# 8_led_51.net
KiCad netlist of a schematic drawn in EasyEDA Pro
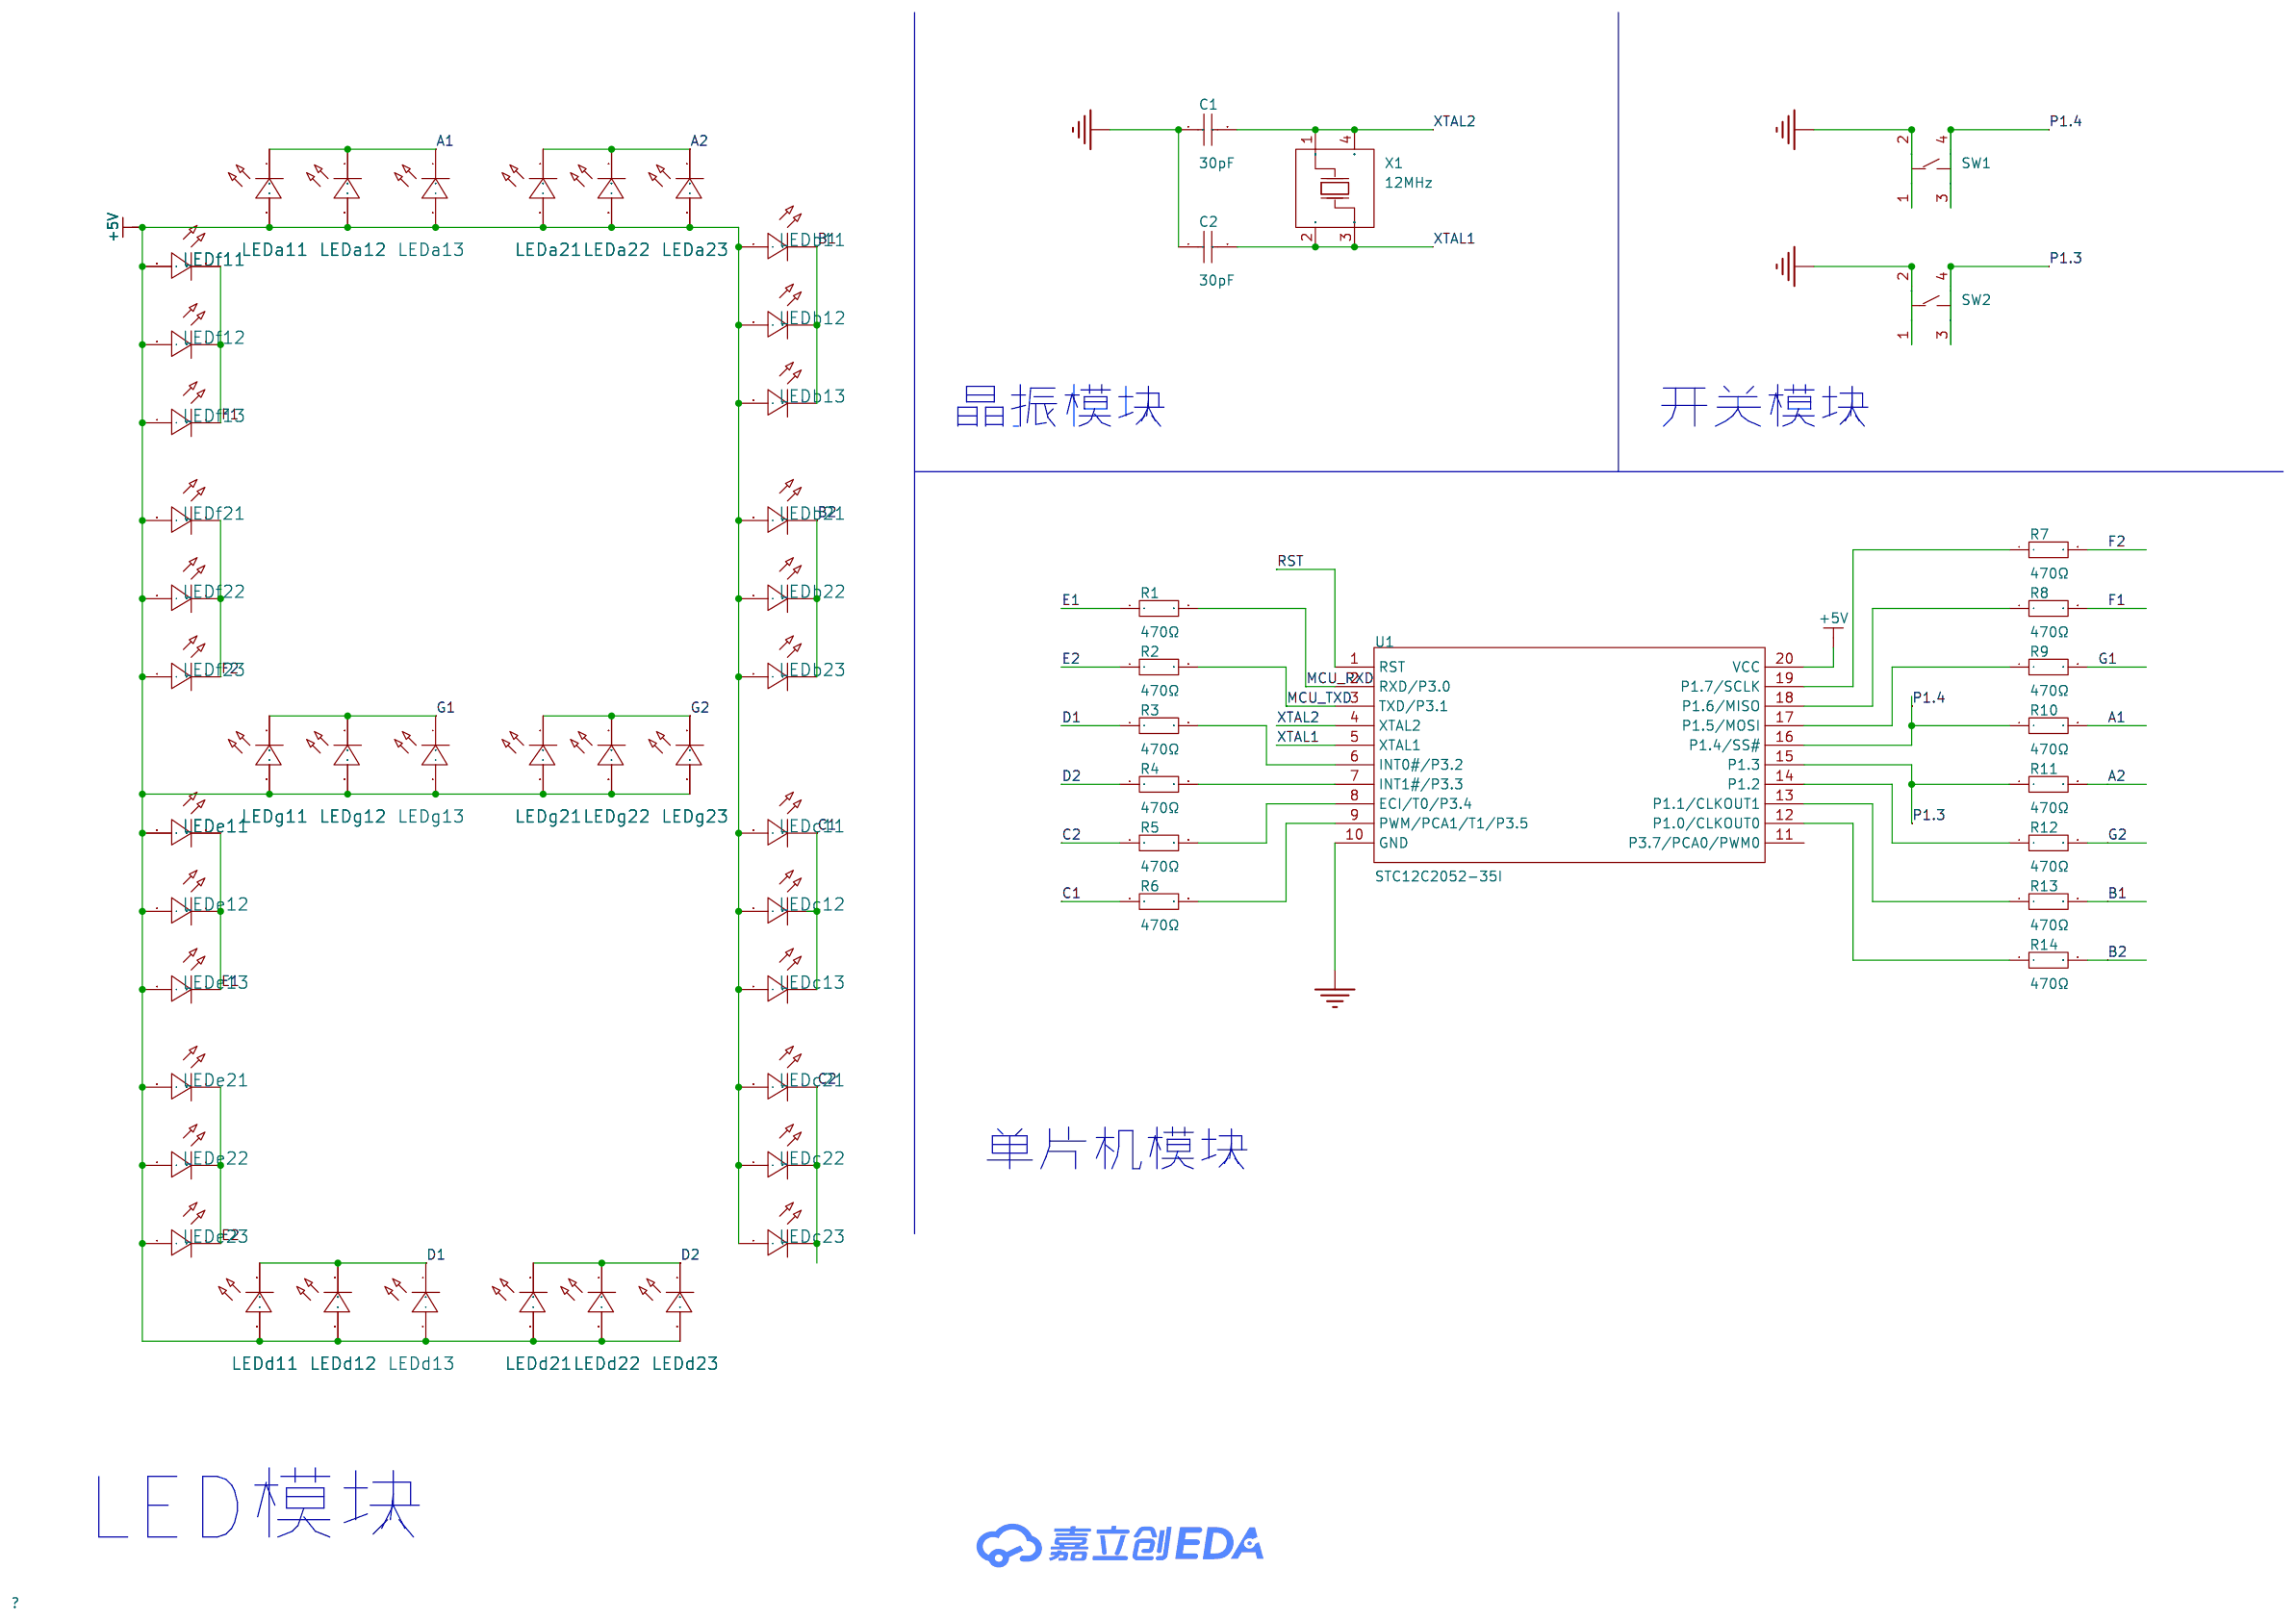
[diagram p0: 主体]
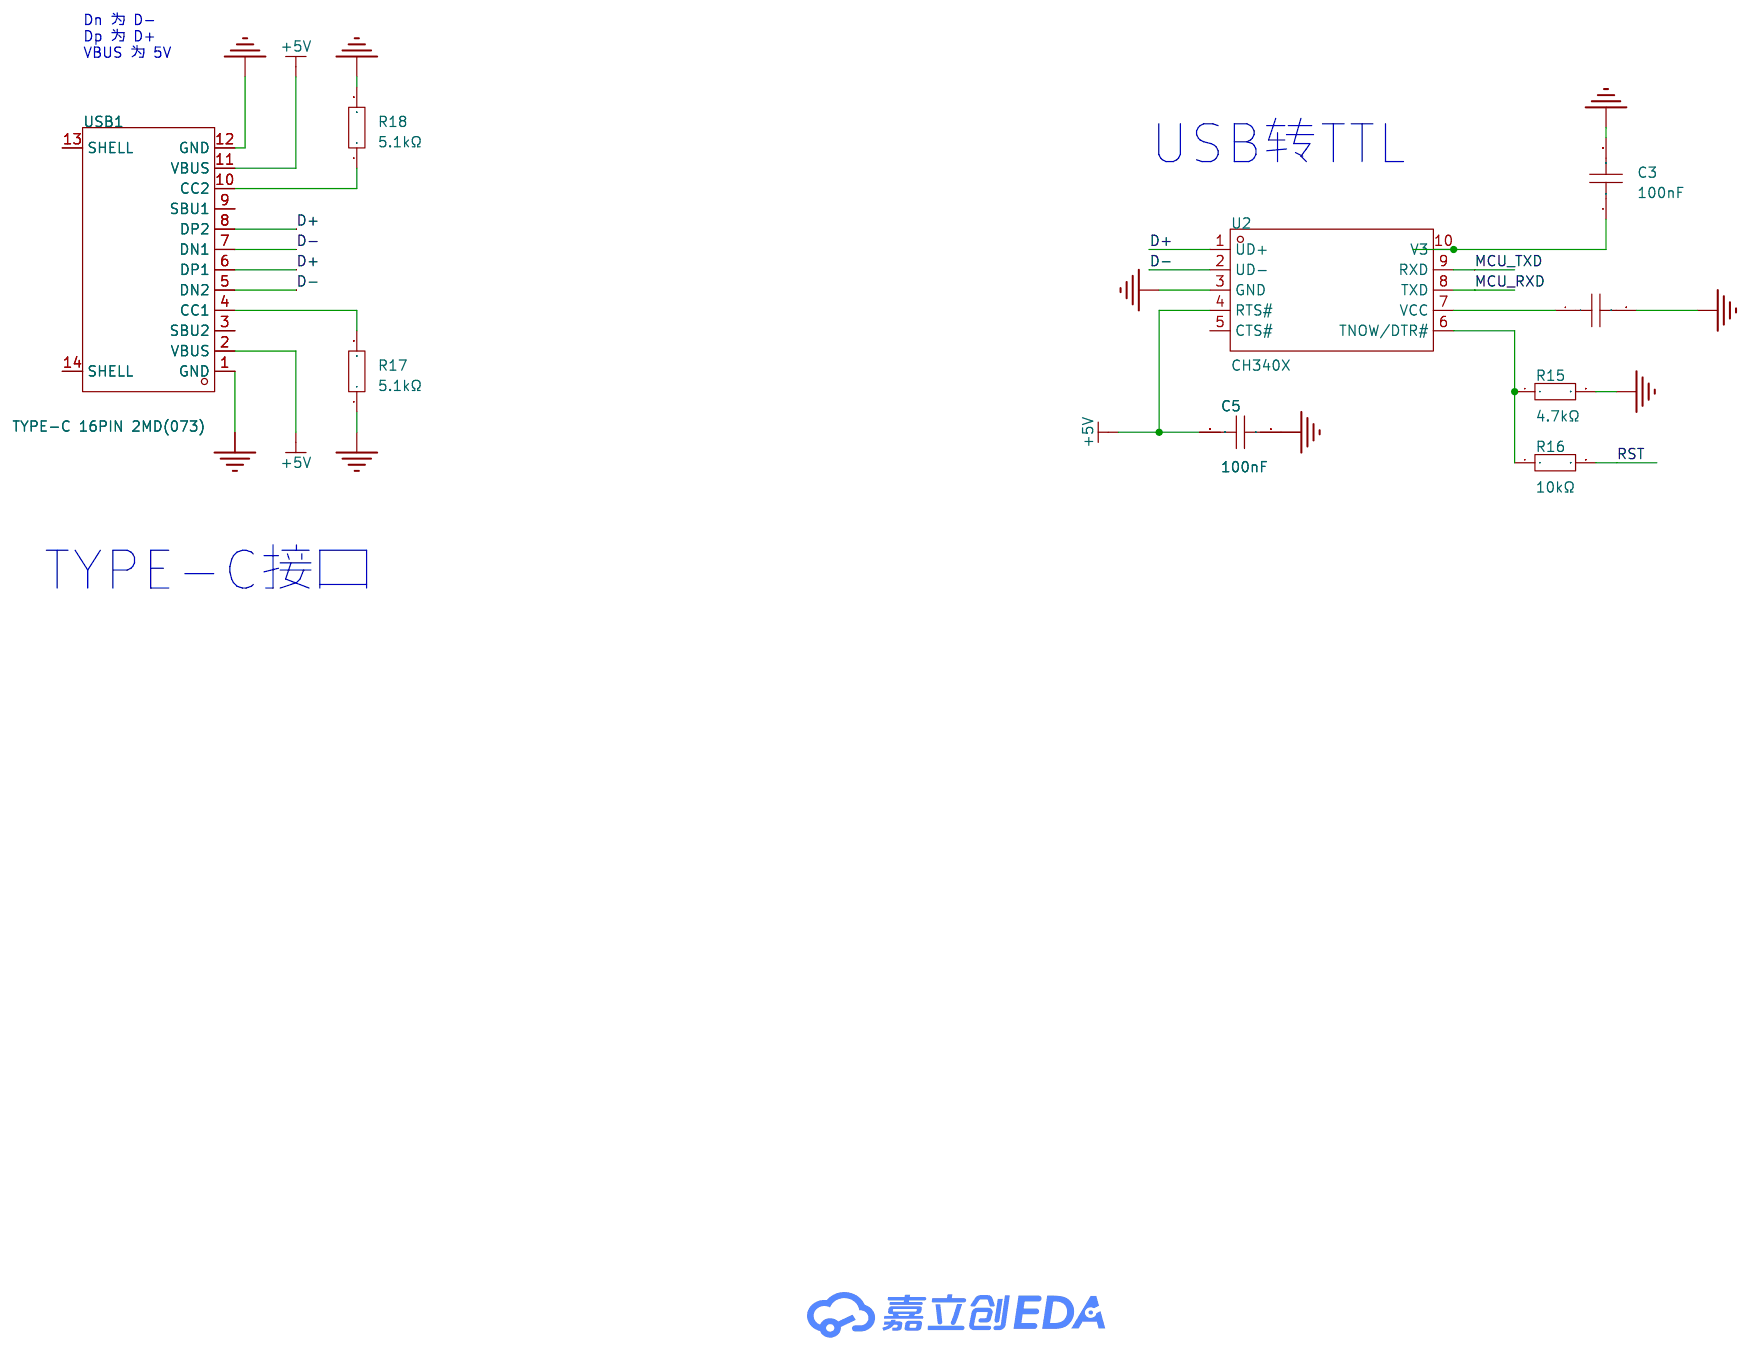
[diagram p1: P2]

(export (version "E")
  (design (tool "Eeschema 10.0.6"))
  (components
    (comp (ref "C1")
      (value "30pF")
      (footprint "easyedapro:C0805")
      (description "容值:30pF;精度:±5%;额定电压:50V;温度系数:C0G;")
      (fields (field (name "Manufacturer Part") "0805CG300J500NT") (field (name "Manufacturer") "FH(风华)"))
      (libsource (lib "easyedapro") (part "0805CG300J500NT"))
    )
    (comp (ref "C2")
      (value "30pF")
      (footprint "easyedapro:C0805")
      (description "容值:30pF;精度:±5%;额定电压:50V;温度系数:C0G;")
      (fields (field (name "Manufacturer Part") "0805CG300J500NT") (field (name "Manufacturer") "FH(风华)"))
      (libsource (lib "easyedapro") (part "0805CG300J500NT"))
    )
    (comp (ref "LEDa11")
      (value "~")
      (footprint "easyedapro:LED_0603")
      (libsource (lib "easyedapro") (part "LED_R"))
    )
    (comp (ref "LEDa12")
      (value "~")
      (footprint "easyedapro:LED_0603")
      (libsource (lib "easyedapro") (part "LED_R"))
    )
    (comp (ref "LEDa13")
      (value "~")
      (footprint "easyedapro:LED_0603")
      (libsource (lib "easyedapro") (part "LED_R"))
    )
    (comp (ref "LEDa21")
      (value "~")
      (footprint "easyedapro:LED_0603")
      (libsource (lib "easyedapro") (part "LED_R"))
    )
    (comp (ref "LEDa22")
      (value "~")
      (footprint "easyedapro:LED_0603")
      (libsource (lib "easyedapro") (part "LED_R"))
    )
    (comp (ref "LEDa23")
      (value "~")
      (footprint "easyedapro:LED_0603")
      (libsource (lib "easyedapro") (part "LED_R"))
    )
    (comp (ref "LEDb11")
      (value "~")
      (footprint "easyedapro:LED_0603")
      (libsource (lib "easyedapro") (part "LED_R"))
    )
    (comp (ref "LEDb12")
      (value "~")
      (footprint "easyedapro:LED_0603")
      (libsource (lib "easyedapro") (part "LED_R"))
    )
    (comp (ref "LEDb13")
      (value "~")
      (footprint "easyedapro:LED_0603")
      (libsource (lib "easyedapro") (part "LED_R"))
    )
    (comp (ref "LEDb21")
      (value "~")
      (footprint "easyedapro:LED_0603")
      (libsource (lib "easyedapro") (part "LED_R"))
    )
    (comp (ref "LEDb22")
      (value "~")
      (footprint "easyedapro:LED_0603")
      (libsource (lib "easyedapro") (part "LED_R"))
    )
    (comp (ref "LEDb23")
      (value "~")
      (footprint "easyedapro:LED_0603")
      (libsource (lib "easyedapro") (part "LED_R"))
    )
    (comp (ref "LEDc11")
      (value "~")
      (footprint "easyedapro:LED_0603")
      (libsource (lib "easyedapro") (part "LED_R"))
    )
    (comp (ref "LEDc12")
      (value "~")
      (footprint "easyedapro:LED_0603")
      (libsource (lib "easyedapro") (part "LED_R"))
    )
    (comp (ref "LEDc13")
      (value "~")
      (footprint "easyedapro:LED_0603")
      (libsource (lib "easyedapro") (part "LED_R"))
    )
    (comp (ref "LEDc21")
      (value "~")
      (footprint "easyedapro:LED_0603")
      (libsource (lib "easyedapro") (part "LED_R"))
    )
    (comp (ref "LEDc22")
      (value "~")
      (footprint "easyedapro:LED_0603")
      (libsource (lib "easyedapro") (part "LED_R"))
    )
    (comp (ref "LEDc23")
      (value "~")
      (footprint "easyedapro:LED_0603")
      (libsource (lib "easyedapro") (part "LED_R"))
    )
    (comp (ref "LEDd11")
      (value "~")
      (footprint "easyedapro:LED_0603")
      (libsource (lib "easyedapro") (part "LED_R"))
    )
    (comp (ref "LEDd12")
      (value "~")
      (footprint "easyedapro:LED_0603")
      (libsource (lib "easyedapro") (part "LED_R"))
    )
    (comp (ref "LEDd13")
      (value "~")
      (footprint "easyedapro:LED_0603")
      (libsource (lib "easyedapro") (part "LED_R"))
    )
    (comp (ref "LEDd21")
      (value "~")
      (footprint "easyedapro:LED_0603")
      (libsource (lib "easyedapro") (part "LED_R"))
    )
    (comp (ref "LEDd22")
      (value "~")
      (footprint "easyedapro:LED_0603")
      (libsource (lib "easyedapro") (part "LED_R"))
    )
    (comp (ref "LEDd23")
      (value "~")
      (footprint "easyedapro:LED_0603")
      (libsource (lib "easyedapro") (part "LED_R"))
    )
    (comp (ref "LEDe11")
      (value "~")
      (footprint "easyedapro:LED_0603")
      (libsource (lib "easyedapro") (part "LED_R"))
    )
    (comp (ref "LEDe12")
      (value "~")
      (footprint "easyedapro:LED_0603")
      (libsource (lib "easyedapro") (part "LED_R"))
    )
    (comp (ref "LEDe13")
      (value "~")
      (footprint "easyedapro:LED_0603")
      (libsource (lib "easyedapro") (part "LED_R"))
    )
    (comp (ref "LEDe21")
      (value "~")
      (footprint "easyedapro:LED_0603")
      (libsource (lib "easyedapro") (part "LED_R"))
    )
    (comp (ref "LEDe22")
      (value "~")
      (footprint "easyedapro:LED_0603")
      (libsource (lib "easyedapro") (part "LED_R"))
    )
    (comp (ref "LEDe23")
      (value "~")
      (footprint "easyedapro:LED_0603")
      (libsource (lib "easyedapro") (part "LED_R"))
    )
    (comp (ref "LEDf11")
      (value "~")
      (footprint "easyedapro:LED_0603")
      (libsource (lib "easyedapro") (part "LED_R"))
    )
    (comp (ref "LEDf12")
      (value "~")
      (footprint "easyedapro:LED_0603")
      (libsource (lib "easyedapro") (part "LED_R"))
    )
    (comp (ref "LEDf13")
      (value "~")
      (footprint "easyedapro:LED_0603")
      (libsource (lib "easyedapro") (part "LED_R"))
    )
    (comp (ref "LEDf21")
      (value "~")
      (footprint "easyedapro:LED_0603")
      (libsource (lib "easyedapro") (part "LED_R"))
    )
    (comp (ref "LEDf22")
      (value "~")
      (footprint "easyedapro:LED_0603")
      (libsource (lib "easyedapro") (part "LED_R"))
    )
    (comp (ref "LEDf23")
      (value "~")
      (footprint "easyedapro:LED_0603")
      (libsource (lib "easyedapro") (part "LED_R"))
    )
    (comp (ref "LEDg11")
      (value "~")
      (footprint "easyedapro:LED_0603")
      (libsource (lib "easyedapro") (part "LED_R"))
    )
    (comp (ref "LEDg12")
      (value "~")
      (footprint "easyedapro:LED_0603")
      (libsource (lib "easyedapro") (part "LED_R"))
    )
    (comp (ref "LEDg13")
      (value "~")
      (footprint "easyedapro:LED_0603")
      (libsource (lib "easyedapro") (part "LED_R"))
    )
    (comp (ref "LEDg21")
      (value "~")
      (footprint "easyedapro:LED_0603")
      (libsource (lib "easyedapro") (part "LED_R"))
    )
    (comp (ref "LEDg22")
      (value "~")
      (footprint "easyedapro:LED_0603")
      (libsource (lib "easyedapro") (part "LED_R"))
    )
    (comp (ref "LEDg23")
      (value "~")
      (footprint "easyedapro:LED_0603")
      (libsource (lib "easyedapro") (part "LED_R"))
    )
    (comp (ref "R1")
      (value "470Ω")
      (footprint "easyedapro:R0805")
      (description "电阻类型:厚膜电阻;阻值:470Ω;精度:±1%;功率:125mW;工作电压:150V;温度系数:±100ppm/°C;")
      (fields
        (field (name "Manufacturer Part") "0805W8F4700T5E")
        (field (name "Manufacturer") "UNI-ROYAL(厚声)")
      )
      (libsource (lib "easyedapro") (part "0805W8F4700T5E"))
    )
    (comp (ref "R2")
      (value "470Ω")
      (footprint "easyedapro:R0805")
      (description "电阻类型:厚膜电阻;阻值:470Ω;精度:±1%;功率:125mW;工作电压:150V;温度系数:±100ppm/°C;")
      (fields
        (field (name "Manufacturer Part") "0805W8F4700T5E")
        (field (name "Manufacturer") "UNI-ROYAL(厚声)")
      )
      (libsource (lib "easyedapro") (part "0805W8F4700T5E"))
    )
    (comp (ref "R3")
      (value "470Ω")
      (footprint "easyedapro:R0805")
      (description "电阻类型:厚膜电阻;阻值:470Ω;精度:±1%;功率:125mW;工作电压:150V;温度系数:±100ppm/°C;")
      (fields
        (field (name "Manufacturer Part") "0805W8F4700T5E")
        (field (name "Manufacturer") "UNI-ROYAL(厚声)")
      )
      (libsource (lib "easyedapro") (part "0805W8F4700T5E"))
    )
    (comp (ref "R4")
      (value "470Ω")
      (footprint "easyedapro:R0805")
      (description "电阻类型:厚膜电阻;阻值:470Ω;精度:±1%;功率:125mW;工作电压:150V;温度系数:±100ppm/°C;")
      (fields
        (field (name "Manufacturer Part") "0805W8F4700T5E")
        (field (name "Manufacturer") "UNI-ROYAL(厚声)")
      )
      (libsource (lib "easyedapro") (part "0805W8F4700T5E"))
    )
    (comp (ref "R5")
      (value "470Ω")
      (footprint "easyedapro:R0805")
      (description "电阻类型:厚膜电阻;阻值:470Ω;精度:±1%;功率:125mW;工作电压:150V;温度系数:±100ppm/°C;")
      (fields
        (field (name "Manufacturer Part") "0805W8F4700T5E")
        (field (name "Manufacturer") "UNI-ROYAL(厚声)")
      )
      (libsource (lib "easyedapro") (part "0805W8F4700T5E"))
    )
    (comp (ref "R6")
      (value "470Ω")
      (footprint "easyedapro:R0805")
      (description "电阻类型:厚膜电阻;阻值:470Ω;精度:±1%;功率:125mW;工作电压:150V;温度系数:±100ppm/°C;")
      (fields
        (field (name "Manufacturer Part") "0805W8F4700T5E")
        (field (name "Manufacturer") "UNI-ROYAL(厚声)")
      )
      (libsource (lib "easyedapro") (part "0805W8F4700T5E"))
    )
    (comp (ref "R7")
      (value "470Ω")
      (footprint "easyedapro:R0805")
      (description "电阻类型:厚膜电阻;阻值:470Ω;精度:±1%;功率:125mW;工作电压:150V;温度系数:±100ppm/°C;")
      (fields
        (field (name "Manufacturer Part") "0805W8F4700T5E")
        (field (name "Manufacturer") "UNI-ROYAL(厚声)")
      )
      (libsource (lib "easyedapro") (part "0805W8F4700T5E"))
    )
    (comp (ref "R8")
      (value "470Ω")
      (footprint "easyedapro:R0805")
      (description "电阻类型:厚膜电阻;阻值:470Ω;精度:±1%;功率:125mW;工作电压:150V;温度系数:±100ppm/°C;")
      (fields
        (field (name "Manufacturer Part") "0805W8F4700T5E")
        (field (name "Manufacturer") "UNI-ROYAL(厚声)")
      )
      (libsource (lib "easyedapro") (part "0805W8F4700T5E"))
    )
    (comp (ref "R9")
      (value "470Ω")
      (footprint "easyedapro:R0805")
      (description "电阻类型:厚膜电阻;阻值:470Ω;精度:±1%;功率:125mW;工作电压:150V;温度系数:±100ppm/°C;")
      (fields
        (field (name "Manufacturer Part") "0805W8F4700T5E")
        (field (name "Manufacturer") "UNI-ROYAL(厚声)")
      )
      (libsource (lib "easyedapro") (part "0805W8F4700T5E"))
    )
    (comp (ref "R10")
      (value "470Ω")
      (footprint "easyedapro:R0805")
      (description "电阻类型:厚膜电阻;阻值:470Ω;精度:±1%;功率:125mW;工作电压:150V;温度系数:±100ppm/°C;")
      (fields
        (field (name "Manufacturer Part") "0805W8F4700T5E")
        (field (name "Manufacturer") "UNI-ROYAL(厚声)")
      )
      (libsource (lib "easyedapro") (part "0805W8F4700T5E"))
    )
    (comp (ref "R11")
      (value "470Ω")
      (footprint "easyedapro:R0805")
      (description "电阻类型:厚膜电阻;阻值:470Ω;精度:±1%;功率:125mW;工作电压:150V;温度系数:±100ppm/°C;")
      (fields
        (field (name "Manufacturer Part") "0805W8F4700T5E")
        (field (name "Manufacturer") "UNI-ROYAL(厚声)")
      )
      (libsource (lib "easyedapro") (part "0805W8F4700T5E"))
    )
    (comp (ref "R12")
      (value "470Ω")
      (footprint "easyedapro:R0805")
      (description "电阻类型:厚膜电阻;阻值:470Ω;精度:±1%;功率:125mW;工作电压:150V;温度系数:±100ppm/°C;")
      (fields
        (field (name "Manufacturer Part") "0805W8F4700T5E")
        (field (name "Manufacturer") "UNI-ROYAL(厚声)")
      )
      (libsource (lib "easyedapro") (part "0805W8F4700T5E"))
    )
    (comp (ref "R13")
      (value "470Ω")
      (footprint "easyedapro:R0805")
      (description "电阻类型:厚膜电阻;阻值:470Ω;精度:±1%;功率:125mW;工作电压:150V;温度系数:±100ppm/°C;")
      (fields
        (field (name "Manufacturer Part") "0805W8F4700T5E")
        (field (name "Manufacturer") "UNI-ROYAL(厚声)")
      )
      (libsource (lib "easyedapro") (part "0805W8F4700T5E"))
    )
    (comp (ref "R14")
      (value "470Ω")
      (footprint "easyedapro:R0805")
      (description "电阻类型:厚膜电阻;阻值:470Ω;精度:±1%;功率:125mW;工作电压:150V;温度系数:±100ppm/°C;")
      (fields
        (field (name "Manufacturer Part") "0805W8F4700T5E")
        (field (name "Manufacturer") "UNI-ROYAL(厚声)")
      )
      (libsource (lib "easyedapro") (part "0805W8F4700T5E"))
    )
    (comp (ref "SW1")
      (value "KH-6X6X5H-STM")
      (footprint "easyedapro:SW-SMD_4P-L6.0-W6.0-P4.50-LS9.0_H5.0")
      (description "电路结构:单刀单掷;按钮形状:圆形按钮;安装方式:立贴;开关长度:6mm;开关宽度:6mm;开关高度:5mm;带支架:不带支架;触点电流:50mA;额定电压:12V;工作寿命:8万次;")
      (fields (field (name "Manufacturer") "kinghelm(金航标)"))
      (libsource (lib "easyedapro") (part "KH-6X6X5H-STM"))
    )
    (comp (ref "SW2")
      (value "KH-6X6X5H-STM")
      (footprint "easyedapro:SW-SMD_4P-L6.0-W6.0-P4.50-LS9.0_H5.0")
      (description "电路结构:单刀单掷;按钮形状:圆形按钮;安装方式:立贴;开关长度:6mm;开关宽度:6mm;开关高度:5mm;带支架:不带支架;触点电流:50mA;额定电压:12V;工作寿命:8万次;")
      (fields (field (name "Manufacturer") "kinghelm(金航标)"))
      (libsource (lib "easyedapro") (part "KH-6X6X5H-STM"))
    )
    (comp (ref "U1")
      (value "STC12C2052-35I")
      (footprint "easyedapro:SOIC-20_L13.0-W7.6-P1.27-LS10.3-BL")
      (description "CPU内核:51系列;CPU最大主频:35MHz;应用领域:-;")
      (fields (field (name "Manufacturer") "STC"))
      (libsource (lib "easyedapro") (part "STC12C2052-35I"))
    )
    (comp (ref "X1")
      (value "12MHz")
      (footprint "easyedapro:CRYSTAL-SMD_4P-L3.2-W2.5-BL")
      (description "晶振类型:贴片晶振;频率:12MHz;常温频差:±10ppm;负载电容:20pF;频率稳定度:±20ppm;")
      (fields (field (name "Manufacturer Part") "X322512MSB4SI") (field (name "Manufacturer") "YXC(扬兴晶振)"))
      (libsource (lib "easyedapro") (part "X322512MSB4SI"))
    )
    (comp (ref "C3")
      (value "100nF")
      (footprint "easyedapro:C0603")
      (description "容值:100nF;精度:±10%;额定电压:50V;温度系数:X7R;")
      (fields
        (field (name "Manufacturer Part") "CL21B104KBCNNNC")
        (field (name "Manufacturer") "SAMSUNG(三星)")
      )
      (libsource (lib "easyedapro") (part "CGA0603X7R104K500JT"))
    )
    (comp (ref "C4")
      (value "100nF")
      (footprint "easyedapro:C0603")
      (description "容值:100nF;精度:±10%;额定电压:50V;温度系数:X7R;")
      (fields
        (field (name "Manufacturer Part") "CL21B104KBCNNNC")
        (field (name "Manufacturer") "SAMSUNG(三星)")
      )
      (libsource (lib "easyedapro") (part "CGA0603X7R104K500JT"))
    )
    (comp (ref "C5")
      (value "100nF")
      (footprint "easyedapro:C0603")
      (description "容值:100nF;精度:±10%;额定电压:50V;温度系数:X7R;")
      (fields
        (field (name "Manufacturer Part") "CL21B104KBCNNNC")
        (field (name "Manufacturer") "SAMSUNG(三星)")
      )
      (libsource (lib "easyedapro") (part "CGA0603X7R104K500JT"))
    )
    (comp (ref "R15")
      (value "4.7kΩ")
      (footprint "easyedapro:R0805")
      (description "电阻类型:厚膜电阻;阻值:4.7kΩ;精度:±1%;功率:125mW;最大工作电压:150V;温度系数:±100ppm/°C;")
      (fields
        (field (name "Manufacturer Part") "0805W8F4701T5E")
        (field (name "Manufacturer") "UNI-ROYAL(厚声)")
      )
      (libsource (lib "easyedapro") (part "0805W8F4701T5E"))
    )
    (comp (ref "R16")
      (value "10kΩ")
      (footprint "easyedapro:R0805")
      (description "电阻类型:厚膜电阻;阻值:10kΩ;精度:±1%;功率:125mW;工作电压:150V;温度系数:±100ppm/°C;")
      (fields
        (field (name "Manufacturer Part") "0805W8F1002T5E")
        (field (name "Manufacturer") "UNI-ROYAL(厚声)")
      )
      (libsource (lib "easyedapro") (part "0805W8F1002T5E"))
    )
    (comp (ref "R17")
      (value "5.1kΩ")
      (footprint "easyedapro:R0805")
      (description "电阻类型:厚膜电阻;阻值:5.1kΩ;精度:±1%;功率:125mW;工作电压:150V;温度系数:±100ppm/°C;")
      (fields
        (field (name "Manufacturer Part") "0805W8F5101T5E")
        (field (name "Manufacturer") "UNI-ROYAL(厚声)")
      )
      (libsource (lib "easyedapro") (part "0805W8F5101T5E"))
    )
    (comp (ref "R18")
      (value "5.1kΩ")
      (footprint "easyedapro:R0805")
      (description "电阻类型:厚膜电阻;阻值:5.1kΩ;精度:±1%;功率:125mW;工作电压:150V;温度系数:±100ppm/°C;")
      (fields
        (field (name "Manufacturer Part") "0805W8F5101T5E")
        (field (name "Manufacturer") "UNI-ROYAL(厚声)")
      )
      (libsource (lib "easyedapro") (part "0805W8F5101T5E"))
    )
    (comp (ref "U2")
      (value "CH340X")
      (footprint "easyedapro:MSOP-10_L3.0-W3.0-P0.50-LS5.0-BL")
      (description "应用功能:USB转串口；USB转并口;USB协议版本:USB 2.0;通道数:-;数据速率:2Mbps;")
      (fields (field (name "Manufacturer") "WCH(南京沁恒)"))
      (libsource (lib "easyedapro") (part "CH340X"))
    )
    (comp (ref "USB1")
      (value "TYPE-C 16PIN 2MD(073)")
      (footprint "easyedapro:USB-C-SMD_TYPE-C-6PIN-2MD-073")
      (description "连接器类型:Type-C;协议标准:-;公母:母;安装方式:卧贴;触点数量:16P;端口数量:1;额定电流 - 电源:3A;工作温度:-25°C~+85°C;")
      (fields (field (name "Manufacturer") "SHOU HAN(首韩)"))
      (libsource (lib "easyedapro") (part "TYPE-C 16PIN 2MD(073)"))
    )
  )
  (nets
    (net (code "1") (name "+5V") (class "Default")
      (node (ref "C5") (pin "2") (pinfunction "2_2") (pintype "unspecified"))
      (node (ref "LEDa11") (pin "2") (pinfunction "A_2") (pintype "input"))
      (node (ref "LEDa12") (pin "2") (pinfunction "A_2") (pintype "input"))
      (node (ref "LEDa13") (pin "2") (pinfunction "A_2") (pintype "input"))
      (node (ref "LEDa21") (pin "2") (pinfunction "A_2") (pintype "input"))
      (node (ref "LEDa22") (pin "2") (pinfunction "A_2") (pintype "input"))
      (node (ref "LEDa23") (pin "2") (pinfunction "A_2") (pintype "input"))
      (node (ref "LEDb11") (pin "2") (pinfunction "A_2") (pintype "input"))
      (node (ref "LEDb12") (pin "2") (pinfunction "A_2") (pintype "input"))
      (node (ref "LEDb13") (pin "2") (pinfunction "A_2") (pintype "input"))
      (node (ref "LEDb21") (pin "2") (pinfunction "A_2") (pintype "input"))
      (node (ref "LEDb22") (pin "2") (pinfunction "A_2") (pintype "input"))
      (node (ref "LEDb23") (pin "2") (pinfunction "A_2") (pintype "input"))
      (node (ref "LEDc11") (pin "2") (pinfunction "A_2") (pintype "input"))
      (node (ref "LEDc12") (pin "2") (pinfunction "A_2") (pintype "input"))
      (node (ref "LEDc13") (pin "2") (pinfunction "A_2") (pintype "input"))
      (node (ref "LEDc21") (pin "2") (pinfunction "A_2") (pintype "input"))
      (node (ref "LEDc22") (pin "2") (pinfunction "A_2") (pintype "input"))
      (node (ref "LEDc23") (pin "2") (pinfunction "A_2") (pintype "input"))
      (node (ref "LEDd11") (pin "2") (pinfunction "A_2") (pintype "input"))
      (node (ref "LEDd12") (pin "2") (pinfunction "A_2") (pintype "input"))
      (node (ref "LEDd13") (pin "2") (pinfunction "A_2") (pintype "input"))
      (node (ref "LEDd21") (pin "2") (pinfunction "A_2") (pintype "input"))
      (node (ref "LEDd22") (pin "2") (pinfunction "A_2") (pintype "input"))
      (node (ref "LEDd23") (pin "2") (pinfunction "A_2") (pintype "input"))
      (node (ref "LEDe11") (pin "2") (pinfunction "A_2") (pintype "input"))
      (node (ref "LEDe12") (pin "2") (pinfunction "A_2") (pintype "input"))
      (node (ref "LEDe13") (pin "2") (pinfunction "A_2") (pintype "input"))
      (node (ref "LEDe21") (pin "2") (pinfunction "A_2") (pintype "input"))
      (node (ref "LEDe22") (pin "2") (pinfunction "A_2") (pintype "input"))
      (node (ref "LEDe23") (pin "2") (pinfunction "A_2") (pintype "input"))
      (node (ref "LEDf11") (pin "2") (pinfunction "A_2") (pintype "input"))
      (node (ref "LEDf12") (pin "2") (pinfunction "A_2") (pintype "input"))
      (node (ref "LEDf13") (pin "2") (pinfunction "A_2") (pintype "input"))
      (node (ref "LEDf21") (pin "2") (pinfunction "A_2") (pintype "input"))
      (node (ref "LEDf22") (pin "2") (pinfunction "A_2") (pintype "input"))
      (node (ref "LEDf23") (pin "2") (pinfunction "A_2") (pintype "input"))
      (node (ref "LEDg11") (pin "2") (pinfunction "A_2") (pintype "input"))
      (node (ref "LEDg12") (pin "2") (pinfunction "A_2") (pintype "input"))
      (node (ref "LEDg13") (pin "2") (pinfunction "A_2") (pintype "input"))
      (node (ref "LEDg21") (pin "2") (pinfunction "A_2") (pintype "input"))
      (node (ref "LEDg22") (pin "2") (pinfunction "A_2") (pintype "input"))
      (node (ref "LEDg23") (pin "2") (pinfunction "A_2") (pintype "input"))
      (node (ref "U1") (pin "20") (pinfunction "VCC_20") (pintype "unspecified"))
      (node (ref "U2") (pin "4") (pinfunction "RTS#_4") (pintype "unspecified"))
      (node (ref "USB1") (pin "11") (pinfunction "VBUS_11") (pintype "unspecified"))
      (node (ref "USB1") (pin "2") (pinfunction "VBUS_2") (pintype "unspecified"))
    )
    (net (code "2") (name "A1") (class "Default")
      (node (ref "LEDa11") (pin "1") (pinfunction "C_1") (pintype "input"))
      (node (ref "LEDa12") (pin "1") (pinfunction "C_1") (pintype "input"))
      (node (ref "LEDa13") (pin "1") (pinfunction "C_1") (pintype "input"))
      (node (ref "R10") (pin "2") (pinfunction "2_2") (pintype "input"))
    )
    (net (code "3") (name "A2") (class "Default")
      (node (ref "LEDa21") (pin "1") (pinfunction "C_1") (pintype "input"))
      (node (ref "LEDa22") (pin "1") (pinfunction "C_1") (pintype "input"))
      (node (ref "LEDa23") (pin "1") (pinfunction "C_1") (pintype "input"))
      (node (ref "R11") (pin "2") (pinfunction "2_2") (pintype "input"))
    )
    (net (code "4") (name "B1") (class "Default")
      (node (ref "LEDb11") (pin "1") (pinfunction "C_1") (pintype "input"))
      (node (ref "LEDb12") (pin "1") (pinfunction "C_1") (pintype "input"))
      (node (ref "LEDb13") (pin "1") (pinfunction "C_1") (pintype "input"))
      (node (ref "R13") (pin "2") (pinfunction "2_2") (pintype "input"))
    )
    (net (code "5") (name "B2") (class "Default")
      (node (ref "LEDb21") (pin "1") (pinfunction "C_1") (pintype "input"))
      (node (ref "LEDb22") (pin "1") (pinfunction "C_1") (pintype "input"))
      (node (ref "LEDb23") (pin "1") (pinfunction "C_1") (pintype "input"))
      (node (ref "R14") (pin "2") (pinfunction "2_2") (pintype "input"))
    )
    (net (code "6") (name "C1") (class "Default")
      (node (ref "LEDc11") (pin "1") (pinfunction "C_1") (pintype "input"))
      (node (ref "LEDc12") (pin "1") (pinfunction "C_1") (pintype "input"))
      (node (ref "LEDc13") (pin "1") (pinfunction "C_1") (pintype "input"))
      (node (ref "R6") (pin "1") (pinfunction "1_1") (pintype "input"))
    )
    (net (code "7") (name "C2") (class "Default")
      (node (ref "LEDc21") (pin "1") (pinfunction "C_1") (pintype "input"))
      (node (ref "LEDc22") (pin "1") (pinfunction "C_1") (pintype "input"))
      (node (ref "LEDc23") (pin "1") (pinfunction "C_1") (pintype "input"))
      (node (ref "R5") (pin "1") (pinfunction "1_1") (pintype "input"))
    )
    (net (code "8") (name "D+") (class "Default")
      (node (ref "U2") (pin "1") (pinfunction "UD+_1") (pintype "unspecified"))
      (node (ref "USB1") (pin "6") (pinfunction "DP1_6") (pintype "unspecified"))
      (node (ref "USB1") (pin "8") (pinfunction "DP2_8") (pintype "unspecified"))
    )
    (net (code "9") (name "D-") (class "Default")
      (node (ref "U2") (pin "2") (pinfunction "UD-_2") (pintype "unspecified"))
      (node (ref "USB1") (pin "5") (pinfunction "DN2_5") (pintype "unspecified"))
      (node (ref "USB1") (pin "7") (pinfunction "DN1_7") (pintype "unspecified"))
    )
    (net (code "10") (name "D1") (class "Default")
      (node (ref "LEDd11") (pin "1") (pinfunction "C_1") (pintype "input"))
      (node (ref "LEDd12") (pin "1") (pinfunction "C_1") (pintype "input"))
      (node (ref "LEDd13") (pin "1") (pinfunction "C_1") (pintype "input"))
      (node (ref "R3") (pin "1") (pinfunction "1_1") (pintype "input"))
    )
    (net (code "11") (name "D2") (class "Default")
      (node (ref "LEDd21") (pin "1") (pinfunction "C_1") (pintype "input"))
      (node (ref "LEDd22") (pin "1") (pinfunction "C_1") (pintype "input"))
      (node (ref "LEDd23") (pin "1") (pinfunction "C_1") (pintype "input"))
      (node (ref "R4") (pin "1") (pinfunction "1_1") (pintype "input"))
    )
    (net (code "12") (name "E1") (class "Default")
      (node (ref "LEDe11") (pin "1") (pinfunction "C_1") (pintype "input"))
      (node (ref "LEDe12") (pin "1") (pinfunction "C_1") (pintype "input"))
      (node (ref "LEDe13") (pin "1") (pinfunction "C_1") (pintype "input"))
      (node (ref "R1") (pin "1") (pinfunction "1_1") (pintype "input"))
    )
    (net (code "13") (name "E2") (class "Default")
      (node (ref "LEDe21") (pin "1") (pinfunction "C_1") (pintype "input"))
      (node (ref "LEDe22") (pin "1") (pinfunction "C_1") (pintype "input"))
      (node (ref "LEDe23") (pin "1") (pinfunction "C_1") (pintype "input"))
      (node (ref "R2") (pin "1") (pinfunction "1_1") (pintype "input"))
    )
    (net (code "14") (name "F1") (class "Default")
      (node (ref "LEDf11") (pin "1") (pinfunction "C_1") (pintype "input"))
      (node (ref "LEDf12") (pin "1") (pinfunction "C_1") (pintype "input"))
      (node (ref "LEDf13") (pin "1") (pinfunction "C_1") (pintype "input"))
      (node (ref "R8") (pin "2") (pinfunction "2_2") (pintype "input"))
    )
    (net (code "15") (name "F2") (class "Default")
      (node (ref "LEDf21") (pin "1") (pinfunction "C_1") (pintype "input"))
      (node (ref "LEDf22") (pin "1") (pinfunction "C_1") (pintype "input"))
      (node (ref "LEDf23") (pin "1") (pinfunction "C_1") (pintype "input"))
      (node (ref "R7") (pin "2") (pinfunction "2_2") (pintype "input"))
    )
    (net (code "16") (name "G1") (class "Default")
      (node (ref "LEDg11") (pin "1") (pinfunction "C_1") (pintype "input"))
      (node (ref "LEDg12") (pin "1") (pinfunction "C_1") (pintype "input"))
      (node (ref "LEDg13") (pin "1") (pinfunction "C_1") (pintype "input"))
      (node (ref "R9") (pin "2") (pinfunction "2_2") (pintype "input"))
    )
    (net (code "17") (name "G2") (class "Default")
      (node (ref "LEDg21") (pin "1") (pinfunction "C_1") (pintype "input"))
      (node (ref "LEDg22") (pin "1") (pinfunction "C_1") (pintype "input"))
      (node (ref "LEDg23") (pin "1") (pinfunction "C_1") (pintype "input"))
      (node (ref "R12") (pin "2") (pinfunction "2_2") (pintype "input"))
    )
    (net (code "18") (name "GND") (class "Default")
      (node (ref "C1") (pin "1") (pinfunction "1_1") (pintype "input"))
      (node (ref "C2") (pin "1") (pinfunction "1_1") (pintype "input"))
      (node (ref "C3") (pin "2") (pinfunction "2_2") (pintype "unspecified"))
      (node (ref "C4") (pin "2") (pinfunction "2_2") (pintype "unspecified"))
      (node (ref "C5") (pin "1") (pinfunction "1_1") (pintype "unspecified"))
      (node (ref "R15") (pin "2") (pinfunction "2_2") (pintype "input"))
      (node (ref "R17") (pin "1") (pinfunction "1_1") (pintype "input"))
      (node (ref "R18") (pin "2") (pinfunction "2_2") (pintype "input"))
      (node (ref "SW1") (pin "1") (pinfunction "1_1") (pintype "unspecified"))
      (node (ref "SW1") (pin "2") (pinfunction "2_2") (pintype "unspecified"))
      (node (ref "SW2") (pin "1") (pinfunction "1_1") (pintype "unspecified"))
      (node (ref "SW2") (pin "2") (pinfunction "2_2") (pintype "unspecified"))
      (node (ref "U1") (pin "10") (pinfunction "GND_10") (pintype "unspecified"))
      (node (ref "U2") (pin "3") (pinfunction "GND_3") (pintype "unspecified"))
      (node (ref "USB1") (pin "1") (pinfunction "GND_1") (pintype "unspecified"))
      (node (ref "USB1") (pin "12") (pinfunction "GND_12") (pintype "unspecified"))
    )
    (net (code "19") (name "MCU_RXD") (class "Default")
      (node (ref "R1") (pin "2") (pinfunction "2_2") (pintype "input"))
      (node (ref "U1") (pin "2") (pinfunction "RXD/P3.0_2") (pintype "unspecified"))
      (node (ref "U2") (pin "8") (pinfunction "TXD_8") (pintype "unspecified"))
    )
    (net (code "20") (name "MCU_TXD") (class "Default")
      (node (ref "R2") (pin "2") (pinfunction "2_2") (pintype "input"))
      (node (ref "U1") (pin "3") (pinfunction "TXD/P3.1_3") (pintype "unspecified"))
      (node (ref "U2") (pin "9") (pinfunction "RXD_9") (pintype "unspecified"))
    )
    (net (code "21") (name "Net-(U1-ECI{slash}T0{slash}P3.4)") (class "Default")
      (node (ref "R5") (pin "2") (pinfunction "2_2") (pintype "input"))
      (node (ref "U1") (pin "8") (pinfunction "ECI/T0/P3.4_8") (pintype "unspecified"))
    )
    (net (code "22") (name "Net-(U1-INT0#{slash}P3.2)") (class "Default")
      (node (ref "R3") (pin "2") (pinfunction "2_2") (pintype "input"))
      (node (ref "U1") (pin "6") (pinfunction "INT0#/P3.2_6") (pintype "unspecified"))
    )
    (net (code "23") (name "Net-(U1-INT1#{slash}P3.3)") (class "Default")
      (node (ref "R4") (pin "2") (pinfunction "2_2") (pintype "input"))
      (node (ref "U1") (pin "7") (pinfunction "INT1#/P3.3_7") (pintype "unspecified"))
    )
    (net (code "24") (name "Net-(U1-P1.0{slash}CLKOUT0)") (class "Default")
      (node (ref "R14") (pin "1") (pinfunction "1_1") (pintype "input"))
      (node (ref "U1") (pin "12") (pinfunction "P1.0/CLKOUT0_12") (pintype "unspecified"))
    )
    (net (code "25") (name "Net-(U1-P1.1{slash}CLKOUT1)") (class "Default")
      (node (ref "R13") (pin "1") (pinfunction "1_1") (pintype "input"))
      (node (ref "U1") (pin "13") (pinfunction "P1.1/CLKOUT1_13") (pintype "unspecified"))
    )
    (net (code "26") (name "Net-(U1-P1.2)") (class "Default")
      (node (ref "R12") (pin "1") (pinfunction "1_1") (pintype "input"))
      (node (ref "U1") (pin "14") (pinfunction "P1.2_14") (pintype "unspecified"))
    )
    (net (code "27") (name "Net-(U1-P1.5{slash}MOSI)") (class "Default")
      (node (ref "R9") (pin "1") (pinfunction "1_1") (pintype "input"))
      (node (ref "U1") (pin "17") (pinfunction "P1.5/MOSI_17") (pintype "unspecified"))
    )
    (net (code "28") (name "Net-(U1-P1.6{slash}MISO)") (class "Default")
      (node (ref "R8") (pin "1") (pinfunction "1_1") (pintype "input"))
      (node (ref "U1") (pin "18") (pinfunction "P1.6/MISO_18") (pintype "unspecified"))
    )
    (net (code "29") (name "Net-(U1-P1.7{slash}SCLK)") (class "Default")
      (node (ref "R7") (pin "1") (pinfunction "1_1") (pintype "input"))
      (node (ref "U1") (pin "19") (pinfunction "P1.7/SCLK_19") (pintype "unspecified"))
    )
    (net (code "30") (name "Net-(U1-PWM{slash}PCA1{slash}T1{slash}P3.5)") (class "Default")
      (node (ref "R6") (pin "2") (pinfunction "2_2") (pintype "input"))
      (node (ref "U1") (pin "9") (pinfunction "PWM/PCA1/T1/P3.5_9") (pintype "unspecified"))
    )
    (net (code "31") (name "Net-(U2-TNOW{slash}DTR#)") (class "Default")
      (node (ref "R15") (pin "1") (pinfunction "1_1") (pintype "input"))
      (node (ref "R16") (pin "1") (pinfunction "1_1") (pintype "input"))
      (node (ref "U2") (pin "6") (pinfunction "TNOW/DTR#_6") (pintype "unspecified"))
    )
    (net (code "32") (name "Net-(U2-V3)") (class "Default")
      (node (ref "C3") (pin "1") (pinfunction "1_1") (pintype "unspecified"))
      (node (ref "U2") (pin "10") (pinfunction "V3_10") (pintype "unspecified"))
    )
    (net (code "33") (name "Net-(U2-VCC)") (class "Default")
      (node (ref "C4") (pin "1") (pinfunction "1_1") (pintype "unspecified"))
      (node (ref "U2") (pin "7") (pinfunction "VCC_7") (pintype "unspecified"))
    )
    (net (code "34") (name "Net-(USB1-CC1)") (class "Default")
      (node (ref "R17") (pin "2") (pinfunction "2_2") (pintype "input"))
      (node (ref "USB1") (pin "4") (pinfunction "CC1_4") (pintype "unspecified"))
    )
    (net (code "35") (name "Net-(USB1-CC2)") (class "Default")
      (node (ref "R18") (pin "1") (pinfunction "1_1") (pintype "input"))
      (node (ref "USB1") (pin "10") (pinfunction "CC2_10") (pintype "unspecified"))
    )
    (net (code "36") (name "P1.3") (class "Default")
      (node (ref "R11") (pin "1") (pinfunction "1_1") (pintype "input"))
      (node (ref "SW2") (pin "3") (pinfunction "3_3") (pintype "unspecified"))
      (node (ref "SW2") (pin "4") (pinfunction "4_4") (pintype "unspecified"))
      (node (ref "U1") (pin "15") (pinfunction "P1.3_15") (pintype "unspecified"))
    )
    (net (code "37") (name "P1.4") (class "Default")
      (node (ref "R10") (pin "1") (pinfunction "1_1") (pintype "input"))
      (node (ref "SW1") (pin "3") (pinfunction "3_3") (pintype "unspecified"))
      (node (ref "SW1") (pin "4") (pinfunction "4_4") (pintype "unspecified"))
      (node (ref "U1") (pin "16") (pinfunction "P1.4/SS#_16") (pintype "unspecified"))
    )
    (net (code "38") (name "RST") (class "Default")
      (node (ref "R16") (pin "2") (pinfunction "2_2") (pintype "input"))
      (node (ref "U1") (pin "1") (pinfunction "RST_1") (pintype "unspecified"))
    )
    (net (code "39") (name "XTAL1") (class "Default")
      (node (ref "C2") (pin "2") (pinfunction "2_2") (pintype "input"))
      (node (ref "U1") (pin "5") (pinfunction "XTAL1_5") (pintype "unspecified"))
      (node (ref "X1") (pin "2") (pinfunction "GND_2") (pintype "unspecified"))
      (node (ref "X1") (pin "3") (pinfunction "OSC2_3") (pintype "unspecified"))
    )
    (net (code "40") (name "XTAL2") (class "Default")
      (node (ref "C1") (pin "2") (pinfunction "2_2") (pintype "input"))
      (node (ref "U1") (pin "4") (pinfunction "XTAL2_4") (pintype "unspecified"))
      (node (ref "X1") (pin "1") (pinfunction "OSC1_1") (pintype "unspecified"))
      (node (ref "X1") (pin "4") (pinfunction "GND_4") (pintype "unspecified"))
    )
    (net (code "41") (name "unconnected-(U1-P3.7{slash}PCA0{slash}PWM0-Pad11)") (class "Default")
      (node (ref "U1") (pin "11") (pinfunction "P3.7/PCA0/PWM0_11") (pintype "unspecified"))
    )
    (net (code "42") (name "unconnected-(U2-CTS#-Pad5)") (class "Default")
      (node (ref "U2") (pin "5") (pinfunction "CTS#_5") (pintype "unspecified"))
    )
    (net (code "43") (name "unconnected-(USB1-SBU1-Pad9)") (class "Default")
      (node (ref "USB1") (pin "9") (pinfunction "SBU1_9") (pintype "unspecified"))
    )
    (net (code "44") (name "unconnected-(USB1-SBU2-Pad3)") (class "Default")
      (node (ref "USB1") (pin "3") (pinfunction "SBU2_3") (pintype "unspecified"))
    )
    (net (code "45") (name "unconnected-(USB1-SHELL-Pad13)") (class "Default")
      (node (ref "USB1") (pin "13") (pinfunction "SHELL_13") (pintype "unspecified"))
    )
    (net (code "46") (name "unconnected-(USB1-SHELL-Pad14)") (class "Default")
      (node (ref "USB1") (pin "14") (pinfunction "SHELL_14") (pintype "unspecified"))
    )
  )
)
